# 03-Headers.net
KiCad netlist of a schematic drawn in Altium Designer
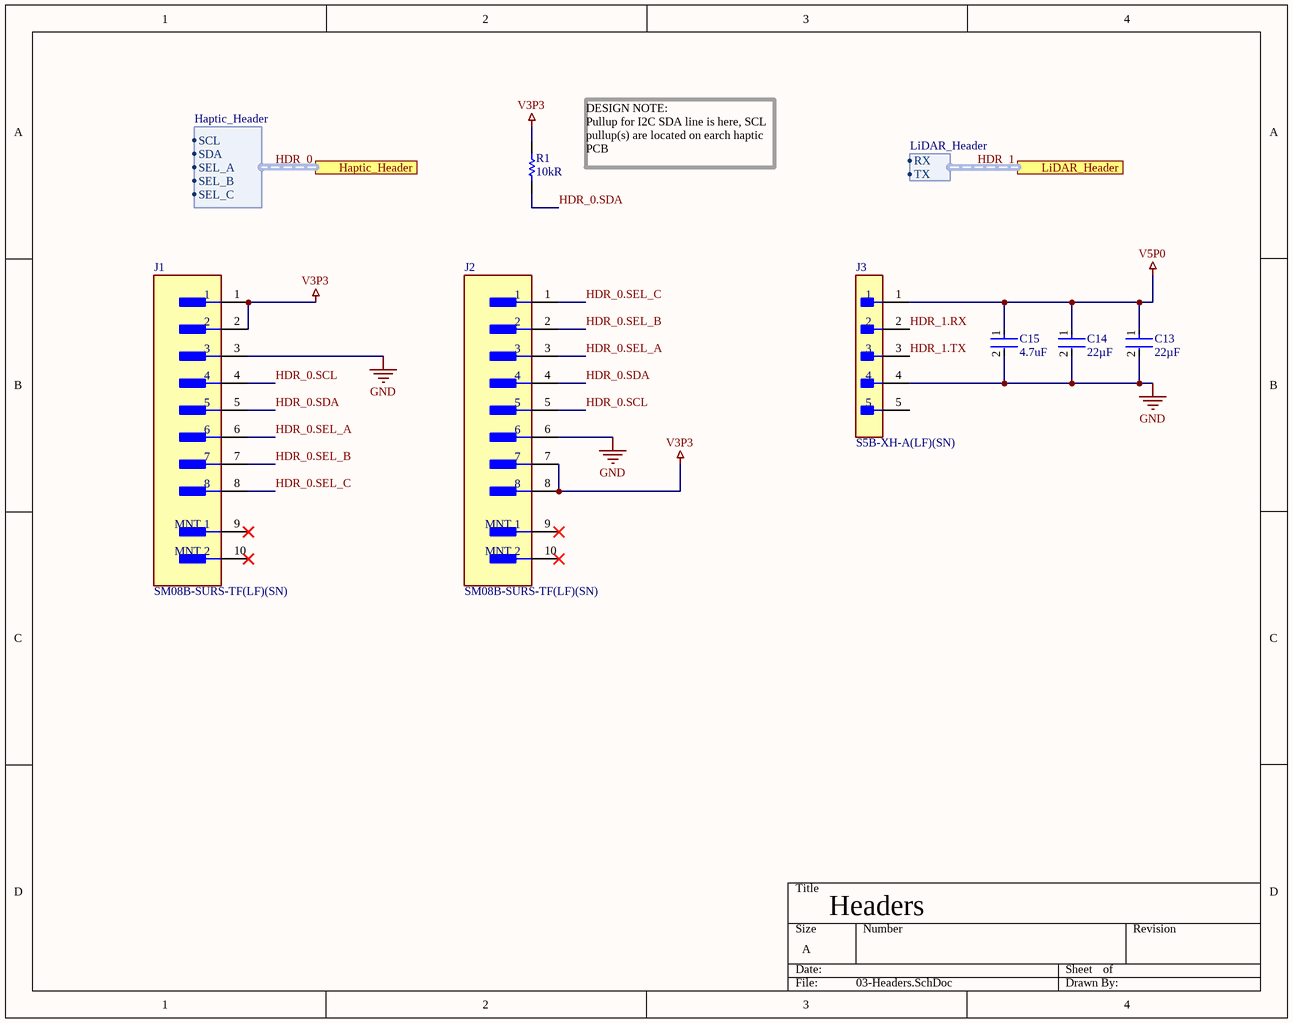
[diagram p0: 03-Headers.SchDoc]

(export (version "E")
  (design (tool "Eeschema 10.0.6"))
  (components
    (comp (ref "C13")
      (value "22µF")
      (footprint "FP-GRM21B-0_2-e0_2_0_7-IPC_B")
      (description "Chip Multilayer Ceramic Capacitors for General Purpose, 0805, 22uF, X7R, 15%, 20%, 10V")
      (libsource (lib "Altium Content Vault") (part "b4654b650e69147ec39a6b967a45e02"))
    )
    (comp (ref "C14")
      (value "22µF")
      (footprint "FP-GRM21B-0_2-e0_2_0_7-IPC_B")
      (description "Chip Multilayer Ceramic Capacitors for General Purpose, 0805, 22uF, X7R, 15%, 20%, 10V")
      (libsource (lib "Altium Content Vault") (part "b4654b650e69147ec39a6b967a45e02"))
    )
    (comp (ref "C15")
      (value "4.7uF")
      (footprint "FP-CC0805-0_85-MFG")
      (description "CC0805MKX7R8BB475\r\nCAP CER 4.7UF 25V X7R 0805")
      (fields
        (field (name "MANUFACTURER") "Yageo")
        (field (name "MANUFACTURER PART NUMBER") "CC0805MKX7R8BB475")
      )
      (libsource (lib "Altium Content Vault") (part "11868f565c42a9108669ba33697ecf6"))
    )
    (comp (ref "J1")
      (value "SM08B-SURS-TF(LF)(SN)")
      (footprint "FP-SM08B-SURS-TF_LF_SN-MFG")
      (description "CONN HEADER SMD R/A 8POS 0.8MM")
      (libsource (lib "Altium Content Vault") (part "0570c48214248da2eadfad1b9356f55"))
    )
    (comp (ref "J2")
      (value "SM08B-SURS-TF(LF)(SN)")
      (footprint "FP-SM08B-SURS-TF_LF_SN-MFG")
      (description "CONN HEADER SMD R/A 8POS 0.8MM")
      (libsource (lib "Altium Content Vault") (part "0570c48214248da2eadfad1b9356f55"))
    )
    (comp (ref "J3")
      (value "S5B-XH-A(LF)(SN)")
      (footprint "FP-S5B-XH-A_LF_SN-MFG")
      (description "CONN HEADER R/A 5POS 2.5MM")
      (libsource (lib "Altium Content Vault") (part "bf93c07fd2649a848d0ec8585582aab"))
    )
    (comp (ref "R1")
      (value "RC0805FR-0710KL")
      (footprint "RESC2013X60X35NL10T20")
      (fields
        (field (name "MANUFACTURER") "Yageo")
        (field (name "RESISTANCE") "10kR")
        (field (name "TOLERANCE") "1%")
      )
      (libsource (lib "Altium Content Vault") (part "RES-2"))
    )
  )
  (nets
    (net (code "3") (name "/HDR_0.SCL") (class "Default")
      (node (ref "J1") (pin "4") (pinfunction "4_4") (pintype "passive"))
      (node (ref "J2") (pin "5") (pinfunction "5_5") (pintype "passive"))
    )
    (net (code "4") (name "/HDR_0.SDA") (class "Default")
      (node (ref "J1") (pin "5") (pinfunction "5_5") (pintype "passive"))
      (node (ref "J2") (pin "4") (pinfunction "4_4") (pintype "passive"))
      (node (ref "R1") (pin "2") (pinfunction "2_2") (pintype "passive"))
    )
    (net (code "5") (name "/HDR_0.SEL_A") (class "Default")
      (node (ref "J1") (pin "6") (pinfunction "6_6") (pintype "passive"))
      (node (ref "J2") (pin "3") (pinfunction "3_3") (pintype "passive"))
    )
    (net (code "6") (name "/HDR_0.SEL_B") (class "Default")
      (node (ref "J1") (pin "7") (pinfunction "7_7") (pintype "passive"))
      (node (ref "J2") (pin "2") (pinfunction "2_2") (pintype "passive"))
    )
    (net (code "7") (name "/HDR_0.SEL_C") (class "Default")
      (node (ref "J1") (pin "8") (pinfunction "8_8") (pintype "passive"))
      (node (ref "J2") (pin "1") (pinfunction "1_1") (pintype "passive"))
    )
    (net (code "9") (name "/HDR_1.RX") (class "Default")
      (node (ref "J3") (pin "2") (pinfunction "2_2") (pintype "passive"))
    )
    (net (code "10") (name "/HDR_1.TX") (class "Default")
      (node (ref "J3") (pin "3") (pinfunction "3_3") (pintype "passive"))
    )
    (net (code "12") (name "GND") (class "Default")
      (node (ref "C13") (pin "2") (pinfunction "2_2") (pintype "passive"))
      (node (ref "C14") (pin "2") (pinfunction "2_2") (pintype "passive"))
      (node (ref "C15") (pin "2") (pinfunction "2_2") (pintype "passive"))
      (node (ref "J1") (pin "3") (pinfunction "3_3") (pintype "passive"))
      (node (ref "J2") (pin "6") (pinfunction "6_6") (pintype "passive"))
      (node (ref "J3") (pin "4") (pinfunction "4_4") (pintype "passive"))
    )
    (net (code "13") (name "V3P3") (class "Default")
      (node (ref "J1") (pin "1") (pinfunction "1_1") (pintype "passive"))
      (node (ref "J1") (pin "2") (pinfunction "2_2") (pintype "passive"))
      (node (ref "J2") (pin "7") (pinfunction "7_7") (pintype "passive"))
      (node (ref "J2") (pin "8") (pinfunction "8_8") (pintype "passive"))
      (node (ref "R1") (pin "1") (pinfunction "1_1") (pintype "passive"))
    )
    (net (code "14") (name "V5P0") (class "Default")
      (node (ref "C13") (pin "1") (pinfunction "1_1") (pintype "passive"))
      (node (ref "C14") (pin "1") (pinfunction "1_1") (pintype "passive"))
      (node (ref "C15") (pin "1") (pinfunction "1_1") (pintype "passive"))
      (node (ref "J3") (pin "1") (pinfunction "1_1") (pintype "passive"))
    )
    (net (code "15") (name "unconnected-(J1-MNT_1-Pad9)") (class "Default")
      (node (ref "J1") (pin "9") (pinfunction "MNT_1_9") (pintype "passive+no_connect"))
    )
    (net (code "16") (name "unconnected-(J1-MNT_2-Pad10)") (class "Default")
      (node (ref "J1") (pin "10") (pinfunction "MNT_2_10") (pintype "passive+no_connect"))
    )
    (net (code "17") (name "unconnected-(J2-MNT_1-Pad9)") (class "Default")
      (node (ref "J2") (pin "9") (pinfunction "MNT_1_9") (pintype "passive+no_connect"))
    )
    (net (code "18") (name "unconnected-(J2-MNT_2-Pad10)") (class "Default")
      (node (ref "J2") (pin "10") (pinfunction "MNT_2_10") (pintype "passive+no_connect"))
    )
    (net (code "19") (name "unconnected-(J3-Pad5)") (class "Default")
      (node (ref "J3") (pin "5") (pinfunction "5_5") (pintype "passive"))
    )
  )
)
